# LoadBoard.net
KiCad netlist of a schematic drawn in EAGLE
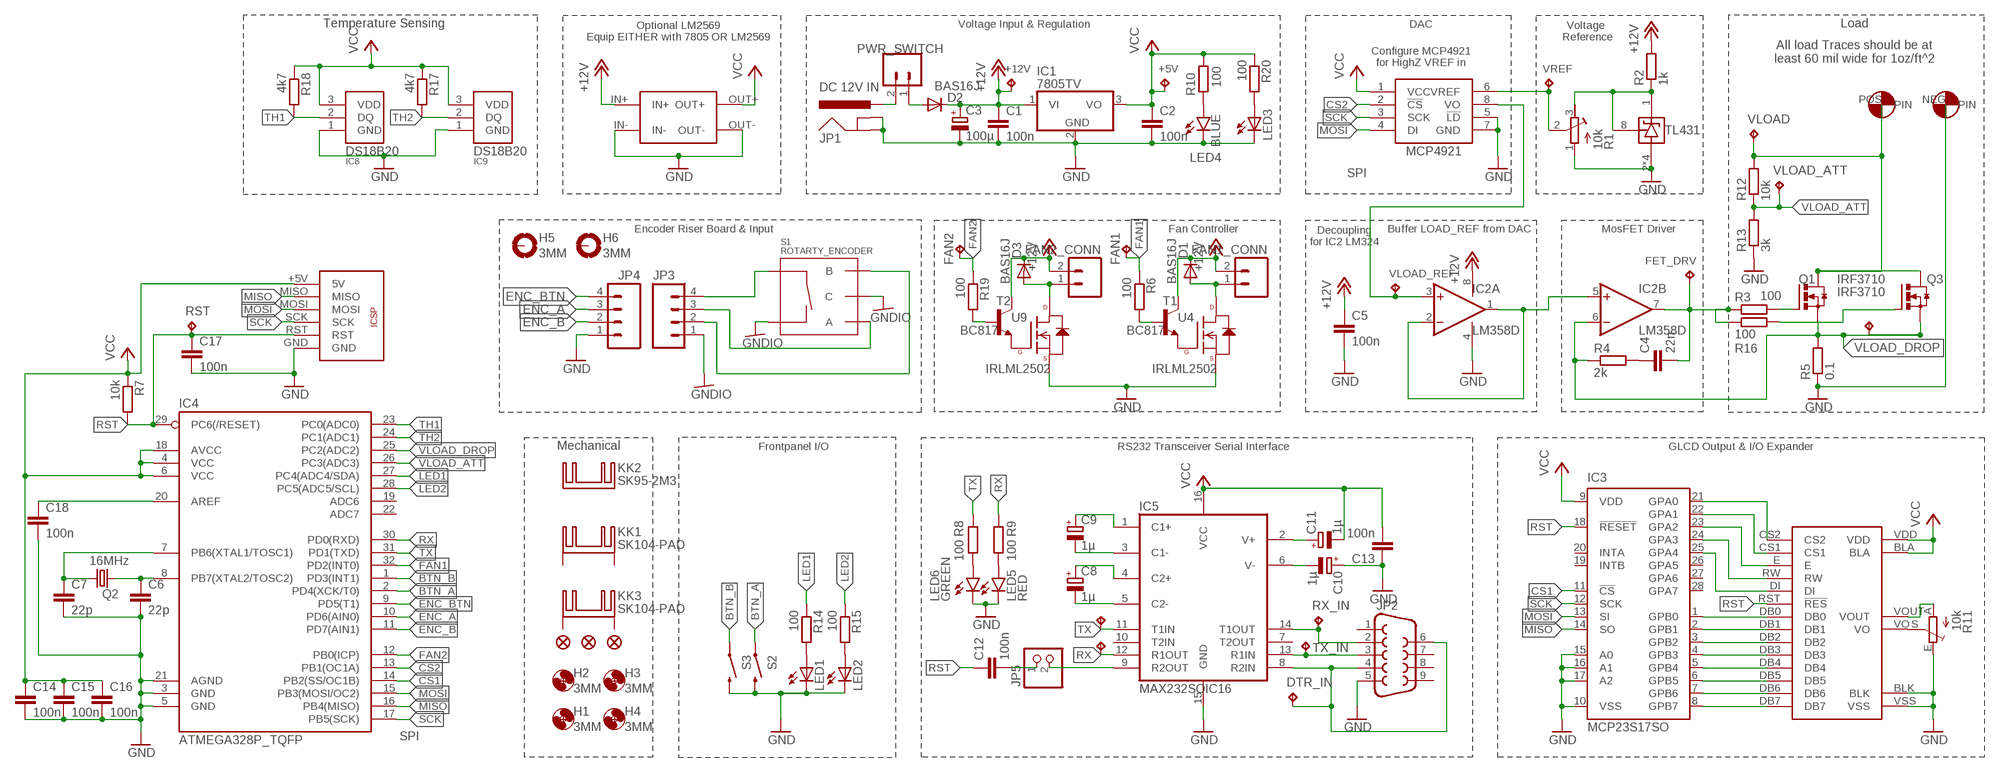
[diagram p0: schematic, sheet 1]

(export (version "E")
  (design (tool "Eeschema 10.0.6"))
  (components
    (comp (ref "+5V")
      (value "TPB1,27")
      (footprint "eagle-import:B1,27")
      (libsource (lib "eagle-import") (part "TPB1,27"))
    )
    (comp (ref "+12V")
      (value "TPB1,27")
      (footprint "eagle-import:B1,27")
      (libsource (lib "eagle-import") (part "TPB1,27"))
    )
    (comp (ref "C1")
      (value "100n")
      (footprint "eagle-import:C1206K")
      (libsource (lib "eagle-import") (part "C-EUC1206K"))
    )
    (comp (ref "C2")
      (value "100n")
      (footprint "eagle-import:C1206K")
      (libsource (lib "eagle-import") (part "C-EUC1206K"))
    )
    (comp (ref "C3")
      (value "100µ")
      (footprint "eagle-import:175TMP-0808")
      (libsource (lib "eagle-import") (part "CPOL-EU175TMP-0808"))
    )
    (comp (ref "C4")
      (value "22n")
      (footprint "eagle-import:C1206")
      (libsource (lib "eagle-import") (part "C-EUC1206"))
    )
    (comp (ref "C5")
      (value "100n")
      (footprint "eagle-import:C1206K")
      (libsource (lib "eagle-import") (part "C-EUC1206K"))
    )
    (comp (ref "C6")
      (value "22p")
      (footprint "eagle-import:C1206K")
      (libsource (lib "eagle-import") (part "C-EUC1206K"))
    )
    (comp (ref "C7")
      (value "22p")
      (footprint "eagle-import:C1206K")
      (libsource (lib "eagle-import") (part "C-EUC1206K"))
    )
    (comp (ref "C8")
      (value "1µ")
      (footprint "eagle-import:153CLV-0405")
      (libsource (lib "eagle-import") (part "CPOL-EU153CLV-0405"))
    )
    (comp (ref "C9")
      (value "1µ")
      (footprint "eagle-import:153CLV-0405")
      (libsource (lib "eagle-import") (part "CPOL-EU153CLV-0405"))
    )
    (comp (ref "C10")
      (value "1µ")
      (footprint "eagle-import:153CLV-0405")
      (libsource (lib "eagle-import") (part "CPOL-EU153CLV-0405"))
    )
    (comp (ref "C11")
      (value "1µ")
      (footprint "eagle-import:153CLV-0405")
      (libsource (lib "eagle-import") (part "CPOL-EU153CLV-0405"))
    )
    (comp (ref "C12")
      (value "100n")
      (footprint "eagle-import:C1206K")
      (libsource (lib "eagle-import") (part "C-EUC1206K"))
    )
    (comp (ref "C13")
      (value "100n")
      (footprint "eagle-import:C1206K")
      (libsource (lib "eagle-import") (part "C-EUC1206K"))
    )
    (comp (ref "C14")
      (value "100n")
      (footprint "eagle-import:C1206K")
      (libsource (lib "eagle-import") (part "C-EUC1206K"))
    )
    (comp (ref "C15")
      (value "100n")
      (footprint "eagle-import:C1206K")
      (libsource (lib "eagle-import") (part "C-EUC1206K"))
    )
    (comp (ref "C16")
      (value "100n")
      (footprint "eagle-import:C1206K")
      (libsource (lib "eagle-import") (part "C-EUC1206K"))
    )
    (comp (ref "C17")
      (value "100n")
      (footprint "eagle-import:C1206K")
      (libsource (lib "eagle-import") (part "C-EUC1206K"))
    )
    (comp (ref "C18")
      (value "100n")
      (footprint "eagle-import:C1206K")
      (libsource (lib "eagle-import") (part "C-EUC1206K"))
    )
    (comp (ref "D1")
      (value "BAS16J")
      (footprint "eagle-import:SOD323-W")
      (libsource (lib "eagle-import") (part "DIODE-SOD323-W"))
    )
    (comp (ref "D2")
      (value "BAS16J")
      (footprint "eagle-import:SOD323-W")
      (libsource (lib "eagle-import") (part "DIODE-SOD323-W"))
    )
    (comp (ref "D3")
      (value "BAS16J")
      (footprint "eagle-import:SOD323-W")
      (libsource (lib "eagle-import") (part "DIODE-SOD323-W"))
    )
    (comp (ref "DTR_IN")
      (value "TPB1,27")
      (footprint "eagle-import:B1,27")
      (libsource (lib "eagle-import") (part "TPB1,27"))
    )
    (comp (ref "FAN1")
      (value "TPB1,27")
      (footprint "eagle-import:B1,27")
      (libsource (lib "eagle-import") (part "TPB1,27"))
    )
    (comp (ref "FAN1_CONN")
      (value "M02POLAR")
      (footprint "eagle-import:MOLEX-1X2")
      (libsource (lib "eagle-import") (part "M02POLAR"))
    )
    (comp (ref "FAN2")
      (value "TPB1,27")
      (footprint "eagle-import:B1,27")
      (libsource (lib "eagle-import") (part "TPB1,27"))
    )
    (comp (ref "FAN2_CONN")
      (value "M02POLAR")
      (footprint "eagle-import:MOLEX-1X2")
      (libsource (lib "eagle-import") (part "M02POLAR"))
    )
    (comp (ref "FET_DRV")
      (value "TPB1,27")
      (footprint "eagle-import:B1,27")
      (libsource (lib "eagle-import") (part "TPB1,27"))
    )
    (comp (ref "FID1")
      (value "FIDUCIAL1X2")
      (footprint "eagle-import:FIDUCIAL-1X2")
      (libsource (lib "eagle-import") (part "FIDUCIAL1X2"))
    )
    (comp (ref "FID2")
      (value "FIDUCIAL1X2")
      (footprint "eagle-import:FIDUCIAL-1X2")
      (libsource (lib "eagle-import") (part "FIDUCIAL1X2"))
    )
    (comp (ref "FID3")
      (value "FIDUCIAL1X2")
      (footprint "eagle-import:FIDUCIAL-1X2")
      (libsource (lib "eagle-import") (part "FIDUCIAL1X2"))
    )
    (comp (ref "H1")
      (value "3MM")
      (footprint "eagle-import:3,0")
      (libsource (lib "eagle-import") (part "MOUNT-HOLE3.0"))
    )
    (comp (ref "H2")
      (value "3MM")
      (footprint "eagle-import:3,0")
      (libsource (lib "eagle-import") (part "MOUNT-HOLE3.0"))
    )
    (comp (ref "H3")
      (value "3MM")
      (footprint "eagle-import:3,0")
      (libsource (lib "eagle-import") (part "MOUNT-HOLE3.0"))
    )
    (comp (ref "H4")
      (value "3MM")
      (footprint "eagle-import:3,0")
      (libsource (lib "eagle-import") (part "MOUNT-HOLE3.0"))
    )
    (comp (ref "H5")
      (value "3MM")
      (footprint "eagle-import:3,0-PAD")
      (libsource (lib "eagle-import") (part "MOUNT-PAD-ROUND3.0"))
    )
    (comp (ref "H6")
      (value "3MM")
      (footprint "eagle-import:3,0-PAD")
      (libsource (lib "eagle-import") (part "MOUNT-PAD-ROUND3.0"))
    )
    (comp (ref "IC1")
      (value "7805TV")
      (footprint "eagle-import:TO220V")
      (libsource (lib "eagle-import") (part "78TV05"))
    )
    (comp (ref "IC2")
      (value "LM358D")
      (footprint "eagle-import:SO08")
      (libsource (lib "eagle-import") (part "LM358D"))
    )
    (comp (ref "IC3")
      (value "MCP23S17SO")
      (footprint "eagle-import:SO28W")
      (fields (field (name "MF") "MICROCHIP") (field (name "MPN") "MCP23S17-E/SO"))
      (libsource (lib "eagle-import") (part "MCP23S17SO"))
    )
    (comp (ref "IC4")
      (value "ATMEGA328P_TQFP")
      (footprint "eagle-import:TQFP32-08")
      (libsource (lib "eagle-import") (part "ATMEGA328P_TQFP"))
    )
    (comp (ref "IC5")
      (value "MAX232SOIC16")
      (footprint "eagle-import:SO016")
      (libsource (lib "eagle-import") (part "MAX232SOIC16"))
    )
    (comp (ref "IC6")
      (value "MCP4921")
      (footprint "eagle-import:SO-8")
      (libsource (lib "eagle-import") (part "MCP4921"))
    )
    (comp (ref "IC7")
      (value "TL431CD")
      (footprint "eagle-import:SO-8")
      (libsource (lib "eagle-import") (part "TL431CD"))
    )
    (comp (ref "IC8")
      (value "DS18B20")
      (footprint "eagle-import:TO-92")
      (libsource (lib "eagle-import") (part "DS18B20"))
    )
    (comp (ref "IC9")
      (value "DS18B20")
      (footprint "eagle-import:TO-92")
      (libsource (lib "eagle-import") (part "DS18B20"))
    )
    (comp (ref "JP1")
      (value "DC 12V IN")
      (footprint "eagle-import:POWER_JACK_PTH")
      (libsource (lib "eagle-import") (part "POWER_JACKPTH"))
    )
    (comp (ref "JP2")
      (value "DB9FEMALE")
      (footprint "eagle-import:DB9")
      (libsource (lib "eagle-import") (part "DB9FEMALE"))
    )
    (comp (ref "JP3")
      (value "M04POLAR")
      (footprint "eagle-import:MOLEX-1X4")
      (libsource (lib "eagle-import") (part "M04POLAR"))
    )
    (comp (ref "JP4")
      (value "M04POLAR")
      (footprint "eagle-import:MOLEX-1X4")
      (libsource (lib "eagle-import") (part "M04POLAR"))
    )
    (comp (ref "JP5")
      (value "PINHD-1X2")
      (footprint "eagle-import:1X02")
      (libsource (lib "eagle-import") (part "PINHD-1X2"))
    )
    (comp (ref "KK1")
      (value "SK104-PAD")
      (footprint "eagle-import:SK104-PAD")
      (libsource (lib "eagle-import") (part "SK104-PAD"))
    )
    (comp (ref "KK2")
      (value "SK95-2M3")
      (footprint "eagle-import:SK95-2M3")
      (libsource (lib "eagle-import") (part "SK95-2M3"))
    )
    (comp (ref "KK3")
      (value "SK104-PAD")
      (footprint "eagle-import:SK104-PAD")
      (libsource (lib "eagle-import") (part "SK104-PAD"))
    )
    (comp (ref "LED1")
      (value "LEDB155")
      (footprint "eagle-import:Q62902-B155")
      (libsource (lib "eagle-import") (part "LEDB155"))
    )
    (comp (ref "LED2")
      (value "LEDB155")
      (footprint "eagle-import:Q62902-B155")
      (libsource (lib "eagle-import") (part "LEDB155"))
    )
    (comp (ref "LED3")
      (value "LEDB155")
      (footprint "eagle-import:Q62902-B155")
      (libsource (lib "eagle-import") (part "LEDB155"))
    )
    (comp (ref "LED4")
      (value "BLUE")
      (footprint "eagle-import:LED-0603")
      (libsource (lib "eagle-import") (part "LED0603"))
    )
    (comp (ref "LED5")
      (value "RED")
      (footprint "eagle-import:LED-0603")
      (libsource (lib "eagle-import") (part "LED0603"))
    )
    (comp (ref "LED6")
      (value "GREEN")
      (footprint "eagle-import:LED-0603")
      (libsource (lib "eagle-import") (part "LED0603"))
    )
    (comp (ref "PWR_SWITCH")
      (value "M02POLAR")
      (footprint "eagle-import:MOLEX-1X2")
      (libsource (lib "eagle-import") (part "M02POLAR"))
    )
    (comp (ref "Q1")
      (value "IRF3710")
      (footprint "eagle-import:TO-220-V")
      (libsource (lib "eagle-import") (part "IRFZ44N"))
    )
    (comp (ref "Q2")
      (value "16MHz")
      (footprint "eagle-import:HC49UP")
      (libsource (lib "eagle-import") (part "CRYSTALHC49UP"))
    )
    (comp (ref "Q3")
      (value "IRF3710")
      (footprint "eagle-import:TO-220-V")
      (libsource (lib "eagle-import") (part "IRFZ44N"))
    )
    (comp (ref "R1")
      (value "10k")
      (footprint "eagle-import:RTRIM3296Y")
      (libsource (lib "eagle-import") (part "R-TRIMM3296Y"))
    )
    (comp (ref "R2")
      (value "1k")
      (footprint "eagle-import:M1206")
      (libsource (lib "eagle-import") (part "R-EU_M1206"))
    )
    (comp (ref "R3")
      (value "100")
      (footprint "eagle-import:R1206")
      (libsource (lib "eagle-import") (part "R-EU_R1206"))
    )
    (comp (ref "R4")
      (value "2k")
      (footprint "eagle-import:R1206")
      (libsource (lib "eagle-import") (part "R-EU_R1206"))
    )
    (comp (ref "R5")
      (value "0.1")
      (footprint "eagle-import:VTA52")
      (libsource (lib "eagle-import") (part "R-EU_VTA52"))
    )
    (comp (ref "R6")
      (value "100")
      (footprint "eagle-import:R1206")
      (libsource (lib "eagle-import") (part "R-EU_R1206"))
    )
    (comp (ref "R7")
      (value "10k")
      (footprint "eagle-import:R1206")
      (libsource (lib "eagle-import") (part "R-EU_R1206"))
    )
    (comp (ref "R8")
      (value "100")
      (footprint "eagle-import:R1206")
      (libsource (lib "eagle-import") (part "R-EU_R1206"))
    )
    (comp (ref "R9")
      (value "100")
      (footprint "eagle-import:R1206")
      (libsource (lib "eagle-import") (part "R-EU_R1206"))
    )
    (comp (ref "R10")
      (value "100")
      (footprint "eagle-import:R1206")
      (libsource (lib "eagle-import") (part "R-EU_R1206"))
    )
    (comp (ref "R11")
      (value "10k")
      (footprint "eagle-import:RS3")
      (libsource (lib "eagle-import") (part "TRIM_EU-RS3"))
    )
    (comp (ref "R12")
      (value "10k")
      (footprint "eagle-import:R1206")
      (libsource (lib "eagle-import") (part "R-EU_R1206"))
    )
    (comp (ref "R13")
      (value "3k")
      (footprint "eagle-import:R1206")
      (libsource (lib "eagle-import") (part "R-EU_R1206"))
    )
    (comp (ref "R14")
      (value "100")
      (footprint "eagle-import:R1206")
      (libsource (lib "eagle-import") (part "R-EU_R1206"))
    )
    (comp (ref "R15")
      (value "100")
      (footprint "eagle-import:R1206")
      (libsource (lib "eagle-import") (part "R-EU_R1206"))
    )
    (comp (ref "R16")
      (value "100")
      (footprint "eagle-import:R1206")
      (libsource (lib "eagle-import") (part "R-EU_R1206"))
    )
    (comp (ref "R17")
      (value "4k7")
      (footprint "eagle-import:M1206")
      (libsource (lib "eagle-import") (part "R-EU_M1206"))
    )
    (comp (ref "R18")
      (value "4k7")
      (footprint "eagle-import:M1206")
      (libsource (lib "eagle-import") (part "R-EU_M1206"))
    )
    (comp (ref "R19")
      (value "100")
      (footprint "eagle-import:R1206")
      (libsource (lib "eagle-import") (part "R-EU_R1206"))
    )
    (comp (ref "R20")
      (value "100")
      (footprint "eagle-import:R1206")
      (libsource (lib "eagle-import") (part "R-EU_R1206"))
    )
    (comp (ref "RST")
      (value "TPB1,27")
      (footprint "eagle-import:B1,27")
      (libsource (lib "eagle-import") (part "TPB1,27"))
    )
    (comp (ref "RX")
      (value "TPB1,27")
      (footprint "eagle-import:B1,27")
      (libsource (lib "eagle-import") (part "TPB1,27"))
    )
    (comp (ref "RX_IN")
      (value "TPB1,27")
      (footprint "eagle-import:B1,27")
      (libsource (lib "eagle-import") (part "TPB1,27"))
    )
    (comp (ref "S1")
      (value "ROTARTY_ENCODER")
      (footprint "eagle-import:ROTARY_ENC_PLAIN")
      (libsource (lib "eagle-import") (part "ROTARTY_ENCODER"))
    )
    (comp (ref "S2")
      (value "SWITCH-MOMENTARY-2SIDE_EZ")
      (footprint "eagle-import:TACTILE-PTH-SIDEEZ")
      (libsource (lib "eagle-import") (part "SWITCH-MOMENTARY-2SIDE_EZ"))
    )
    (comp (ref "S3")
      (value "SWITCH-MOMENTARY-2SIDE_EZ")
      (footprint "eagle-import:TACTILE-PTH-SIDEEZ")
      (libsource (lib "eagle-import") (part "SWITCH-MOMENTARY-2SIDE_EZ"))
    )
    (comp (ref "T1")
      (value "BC817")
      (footprint "eagle-import:SOT23-BEC")
      (libsource (lib "eagle-import") (part "-NPN-SOT23-BECBC817"))
    )
    (comp (ref "T2")
      (value "BC817")
      (footprint "eagle-import:SOT23-BEC")
      (libsource (lib "eagle-import") (part "-NPN-SOT23-BECBC817"))
    )
    (comp (ref "TX")
      (value "TPB1,27")
      (footprint "eagle-import:B1,27")
      (libsource (lib "eagle-import") (part "TPB1,27"))
    )
    (comp (ref "TX_IN")
      (value "TPB1,27")
      (footprint "eagle-import:B1,27")
      (libsource (lib "eagle-import") (part "TPB1,27"))
    )
    (comp (ref "U$3")
      (value "CON-2-HIGAMP")
      (footprint "eagle-import:CON-HIGHAMP-0.3_")
      (libsource (lib "eagle-import") (part "CON-2-HIGAMP"))
    )
    (comp (ref "U$5")
      (value "ICSPTHROUGHHOLE")
      (footprint "eagle-import:ICSP-THROUGHHOLE")
      (libsource (lib "eagle-import") (part "ICSPTHROUGHHOLE"))
    )
    (comp (ref "U$6")
      (value "KS0108-GLCDS6B0108")
      (footprint "eagle-import:KS0108-S6B0108-GLCD")
      (libsource (lib "eagle-import") (part "KS0108-GLCDS6B0108"))
    )
    (comp (ref "U$10")
      (value "LM2569NO_OUTLINE")
      (footprint "eagle-import:LM2596_NO_OUTLINE")
      (libsource (lib "eagle-import") (part "LM2569NO_OUTLINE"))
    )
    (comp (ref "U4")
      (value "IRLML2502")
      (footprint "eagle-import:SOT23-3")
      (libsource (lib "eagle-import") (part "N-CHANNEL-MOSFET-BSS138"))
    )
    (comp (ref "U9")
      (value "IRLML2502")
      (footprint "eagle-import:SOT23-3")
      (libsource (lib "eagle-import") (part "N-CHANNEL-MOSFET-BSS138"))
    )
    (comp (ref "VLOAD")
      (value "TPB1,27")
      (footprint "eagle-import:B1,27")
      (libsource (lib "eagle-import") (part "TPB1,27"))
    )
    (comp (ref "VLOAD_ATT")
      (value "TPB1,27")
      (footprint "eagle-import:B1,27")
      (libsource (lib "eagle-import") (part "TPB1,27"))
    )
    (comp (ref "VLOAD_DROP")
      (value "TPB1,27")
      (footprint "eagle-import:B1,27")
      (libsource (lib "eagle-import") (part "TPB1,27"))
    )
    (comp (ref "VLOAD_REF")
      (value "TPB1,27")
      (footprint "eagle-import:B1,27")
      (libsource (lib "eagle-import") (part "TPB1,27"))
    )
    (comp (ref "VREF")
      (value "TPB1,27")
      (footprint "eagle-import:B1,27")
      (libsource (lib "eagle-import") (part "TPB1,27"))
    )
  )
  (nets
    (net (code "1") (name "+12V") (class "Default")
      (node (ref "+12V") (pin "TP") (pinfunction "TP_TP") (pintype "input"))
      (node (ref "C1") (pin "1") (pinfunction "1_1") (pintype "passive"))
      (node (ref "C3") (pin "+") (pinfunction "+_+") (pintype "passive"))
      (node (ref "C5") (pin "1") (pinfunction "1_1") (pintype "passive"))
      (node (ref "D1") (pin "C") (pinfunction "C_C") (pintype "passive"))
      (node (ref "D2") (pin "C") (pinfunction "C_C") (pintype "passive"))
      (node (ref "D3") (pin "C") (pinfunction "C_C") (pintype "passive"))
      (node (ref "FAN1_CONN") (pin "2") (pinfunction "2_2") (pintype "passive"))
      (node (ref "FAN2_CONN") (pin "2") (pinfunction "2_2") (pintype "passive"))
      (node (ref "IC1") (pin "1") (pinfunction "VI_1") (pintype "input"))
      (node (ref "IC2") (pin "8") (pinfunction "V+_8") (pintype "power_in"))
      (node (ref "R2") (pin "2") (pinfunction "2_2") (pintype "passive"))
      (node (ref "T1") (pin "C") (pinfunction "C_C") (pintype "passive"))
      (node (ref "T2") (pin "C") (pinfunction "C_C") (pintype "passive"))
      (node (ref "U$10") (pin "IN+") (pinfunction "IN+_IN+") (pintype "bidirectional"))
    )
    (net (code "2") (name "BTN_A") (class "Default")
      (node (ref "IC4") (pin "2") (pinfunction "PD4(XCK/T0)_2") (pintype "bidirectional"))
      (node (ref "S2") (pin "1") (pinfunction "1_1") (pintype "passive"))
    )
    (net (code "3") (name "BTN_B") (class "Default")
      (node (ref "IC4") (pin "1") (pinfunction "PD3(INT1)_1") (pintype "bidirectional"))
      (node (ref "S3") (pin "1") (pinfunction "1_1") (pintype "passive"))
    )
    (net (code "4") (name "CS1") (class "Default")
      (node (ref "IC3") (pin "11") (pinfunction "~{CS}_11") (pintype "input"))
      (node (ref "IC4") (pin "14") (pinfunction "PB2(SS/OC1B)_14") (pintype "bidirectional"))
    )
    (net (code "5") (name "CS2") (class "Default")
      (node (ref "IC4") (pin "13") (pinfunction "PB1(OC1A)_13") (pintype "bidirectional"))
      (node (ref "IC6") (pin "2") (pinfunction "~{CS}_2") (pintype "bidirectional"))
    )
    (net (code "6") (name "ENC_A") (class "Default")
      (node (ref "IC4") (pin "10") (pinfunction "PD6(AIN0)_10") (pintype "bidirectional"))
      (node (ref "JP4") (pin "3") (pinfunction "3_3") (pintype "passive"))
    )
    (net (code "7") (name "ENC_B") (class "Default")
      (node (ref "IC4") (pin "11") (pinfunction "PD7(AIN1)_11") (pintype "bidirectional"))
      (node (ref "JP4") (pin "2") (pinfunction "2_2") (pintype "passive"))
    )
    (net (code "8") (name "ENC_BTN") (class "Default")
      (node (ref "IC4") (pin "9") (pinfunction "PD5(T1)_9") (pintype "bidirectional"))
      (node (ref "JP4") (pin "4") (pinfunction "4_4") (pintype "passive"))
    )
    (net (code "9") (name "FAN1") (class "Default")
      (node (ref "FAN1") (pin "TP") (pinfunction "TP_TP") (pintype "input"))
      (node (ref "IC4") (pin "32") (pinfunction "PD2(INT0)_32") (pintype "bidirectional"))
      (node (ref "R6") (pin "1") (pinfunction "1_1") (pintype "passive"))
    )
    (net (code "10") (name "FAN2") (class "Default")
      (node (ref "FAN2") (pin "TP") (pinfunction "TP_TP") (pintype "input"))
      (node (ref "IC4") (pin "12") (pinfunction "PB0(ICP)_12") (pintype "bidirectional"))
      (node (ref "R19") (pin "1") (pinfunction "1_1") (pintype "passive"))
    )
    (net (code "11") (name "GND") (class "Default")
      (node (ref "C1") (pin "2") (pinfunction "2_2") (pintype "passive"))
      (node (ref "C10") (pin "+") (pinfunction "+_+") (pintype "passive"))
      (node (ref "C13") (pin "1") (pinfunction "1_1") (pintype "passive"))
      (node (ref "C14") (pin "2") (pinfunction "2_2") (pintype "passive"))
      (node (ref "C15") (pin "2") (pinfunction "2_2") (pintype "passive"))
      (node (ref "C16") (pin "2") (pinfunction "2_2") (pintype "passive"))
      (node (ref "C17") (pin "2") (pinfunction "2_2") (pintype "passive"))
      (node (ref "C18") (pin "2") (pinfunction "2_2") (pintype "passive"))
      (node (ref "C2") (pin "2") (pinfunction "2_2") (pintype "passive"))
      (node (ref "C3") (pin "-") (pinfunction "-_-") (pintype "passive"))
      (node (ref "C5") (pin "2") (pinfunction "2_2") (pintype "passive"))
      (node (ref "C6") (pin "2") (pinfunction "2_2") (pintype "passive"))
      (node (ref "C7") (pin "2") (pinfunction "2_2") (pintype "passive"))
      (node (ref "IC1") (pin "2") (pinfunction "GND_2") (pintype "passive"))
      (node (ref "IC2") (pin "4") (pinfunction "V-_4") (pintype "power_in"))
      (node (ref "IC3") (pin "10") (pinfunction "VSS_10") (pintype "power_in"))
      (node (ref "IC3") (pin "15") (pinfunction "A0_15") (pintype "input"))
      (node (ref "IC3") (pin "16") (pinfunction "A1_16") (pintype "input"))
      (node (ref "IC3") (pin "17") (pinfunction "A2_17") (pintype "input"))
      (node (ref "IC4") (pin "21") (pinfunction "AGND_21") (pintype "bidirectional"))
      (node (ref "IC4") (pin "3") (pinfunction "GND_3") (pintype "bidirectional"))
      (node (ref "IC4") (pin "5") (pinfunction "GND_5") (pintype "bidirectional"))
      (node (ref "IC5") (pin "15") (pinfunction "GND_15") (pintype "bidirectional"))
      (node (ref "IC6") (pin "5") (pinfunction "~{LD}_5") (pintype "input"))
      (node (ref "IC6") (pin "7") (pinfunction "GND_7") (pintype "power_in"))
      (node (ref "IC7") (pin "2") (pinfunction "ANODE_2") (pintype "passive"))
      (node (ref "IC7") (pin "3") (pinfunction "ANODE_3") (pintype "passive"))
      (node (ref "IC7") (pin "6") (pinfunction "ANODE_6") (pintype "passive"))
      (node (ref "IC7") (pin "7") (pinfunction "ANODE_7") (pintype "passive"))
      (node (ref "IC8") (pin "1") (pinfunction "GND_1") (pintype "power_in"))
      (node (ref "IC9") (pin "1") (pinfunction "GND_1") (pintype "power_in"))
      (node (ref "JP1") (pin "GND") (pinfunction "GND_GND") (pintype "bidirectional"))
      (node (ref "JP1") (pin "GNDBREAK") (pinfunction "GNDBREAK_GNDBREAK") (pintype "bidirectional"))
      (node (ref "JP2") (pin "5") (pinfunction "5_5") (pintype "passive"))
      (node (ref "JP4") (pin "1") (pinfunction "1_1") (pintype "passive"))
      (node (ref "LED1") (pin "K") (pinfunction "C_K") (pintype "passive"))
      (node (ref "LED2") (pin "K") (pinfunction "C_K") (pintype "passive"))
      (node (ref "LED3") (pin "K") (pinfunction "C_K") (pintype "passive"))
      (node (ref "LED4") (pin "C") (pinfunction "C_C") (pintype "passive"))
      (node (ref "LED5") (pin "C") (pinfunction "C_C") (pintype "passive"))
      (node (ref "LED6") (pin "C") (pinfunction "C_C") (pintype "passive"))
      (node (ref "R1") (pin "1") (pinfunction "A_1") (pintype "passive"))
      (node (ref "R11") (pin "E") (pinfunction "E_E") (pintype "passive"))
      (node (ref "R13") (pin "1") (pinfunction "1_1") (pintype "passive"))
      (node (ref "R5") (pin "1") (pinfunction "1_1") (pintype "passive"))
      (node (ref "S2") (pin "2") (pinfunction "2_2") (pintype "passive"))
      (node (ref "S3") (pin "2") (pinfunction "2_2") (pintype "passive"))
      (node (ref "U$10") (pin "IN-") (pinfunction "IN-_IN-") (pintype "bidirectional"))
      (node (ref "U$10") (pin "OUT-") (pinfunction "OUT-_OUT-") (pintype "bidirectional"))
      (node (ref "U$3") (pin "NEG") (pinfunction "PIN_NEG") (pintype "bidirectional"))
      (node (ref "U$5") (pin "GND") (pinfunction "GND_GND") (pintype "bidirectional"))
      (node (ref "U$6") (pin "BLK") (pinfunction "BLK_BLK") (pintype "bidirectional"))
      (node (ref "U$6") (pin "VSS") (pinfunction "VSS_VSS") (pintype "bidirectional"))
      (node (ref "U4") (pin "2") (pinfunction "S_2") (pintype "passive"))
      (node (ref "U9") (pin "2") (pinfunction "S_2") (pintype "passive"))
    )
    (net (code "12") (name "GNDIO") (class "Default")
      (node (ref "JP3") (pin "1") (pinfunction "1_1") (pintype "passive"))
      (node (ref "S1") (pin "C") (pinfunction "C_C") (pintype "bidirectional"))
      (node (ref "S1") (pin "SW-") (pinfunction "SW-_SW-") (pintype "bidirectional"))
    )
    (net (code "13") (name "LED1") (class "Default")
      (node (ref "IC4") (pin "27") (pinfunction "PC4(ADC4/SDA)_27") (pintype "bidirectional"))
      (node (ref "R14") (pin "1") (pinfunction "1_1") (pintype "passive"))
    )
    (net (code "14") (name "LED2") (class "Default")
      (node (ref "IC4") (pin "28") (pinfunction "PC5(ADC5/SCL)_28") (pintype "bidirectional"))
      (node (ref "R15") (pin "1") (pinfunction "1_1") (pintype "passive"))
    )
    (net (code "15") (name "MISO") (class "Default")
      (node (ref "IC3") (pin "14") (pinfunction "SO_14") (pintype "output"))
      (node (ref "IC4") (pin "16") (pinfunction "PB4(MISO)_16") (pintype "bidirectional"))
      (node (ref "U$5") (pin "MISO") (pinfunction "MISO_MISO") (pintype "bidirectional"))
    )
    (net (code "16") (name "MOSI") (class "Default")
      (node (ref "IC3") (pin "13") (pinfunction "SI_13") (pintype "input"))
      (node (ref "IC4") (pin "15") (pinfunction "PB3(MOSI/OC2)_15") (pintype "bidirectional"))
      (node (ref "IC6") (pin "4") (pinfunction "DI_4") (pintype "bidirectional"))
      (node (ref "U$5") (pin "MOSI") (pinfunction "MOSI_MOSI") (pintype "bidirectional"))
    )
    (net (code "17") (name "Net-(C4-Pad1)") (class "Default")
      (node (ref "C4") (pin "1") (pinfunction "1_1") (pintype "passive"))
      (node (ref "R4") (pin "2") (pinfunction "2_2") (pintype "passive"))
    )
    (net (code "18") (name "Net-(C12-Pad2)") (class "Default")
      (node (ref "C12") (pin "2") (pinfunction "2_2") (pintype "passive"))
      (node (ref "JP5") (pin "1") (pinfunction "1_1") (pintype "passive"))
    )
    (net (code "19") (name "Net-(D2-PadA)") (class "Default")
      (node (ref "D2") (pin "A") (pinfunction "A_A") (pintype "passive"))
      (node (ref "PWR_SWITCH") (pin "1") (pinfunction "1_1") (pintype "passive"))
    )
    (net (code "20") (name "Net-(IC2A-+IN)") (class "Default")
      (node (ref "IC2") (pin "3") (pinfunction "+IN_3") (pintype "input"))
      (node (ref "IC6") (pin "8") (pinfunction "VO_8") (pintype "output"))
      (node (ref "VLOAD_REF") (pin "TP") (pinfunction "TP_TP") (pintype "input"))
    )
    (net (code "21") (name "Net-(IC2A--IN)") (class "Default")
      (node (ref "IC2") (pin "1") (pinfunction "OUT_1") (pintype "output"))
      (node (ref "IC2") (pin "2") (pinfunction "-IN_2") (pintype "input"))
      (node (ref "IC2") (pin "5") (pinfunction "+IN_5") (pintype "input"))
    )
    (net (code "22") (name "Net-(IC2B-OUT)") (class "Default")
      (node (ref "C4") (pin "2") (pinfunction "2_2") (pintype "passive"))
      (node (ref "FET_DRV") (pin "TP") (pinfunction "TP_TP") (pintype "input"))
      (node (ref "IC2") (pin "7") (pinfunction "OUT_7") (pintype "output"))
      (node (ref "R16") (pin "1") (pinfunction "1_1") (pintype "passive"))
      (node (ref "R3") (pin "1") (pinfunction "1_1") (pintype "passive"))
    )
    (net (code "23") (name "Net-(IC3-GPA0)") (class "Default")
      (node (ref "IC3") (pin "21") (pinfunction "GPA0_21") (pintype "bidirectional"))
      (node (ref "U$6") (pin "CS2") (pinfunction "CS2_CS2") (pintype "bidirectional"))
    )
    (net (code "24") (name "Net-(IC3-GPA1)") (class "Default")
      (node (ref "IC3") (pin "22") (pinfunction "GPA1_22") (pintype "bidirectional"))
      (node (ref "U$6") (pin "CS1") (pinfunction "CS1_CS1") (pintype "bidirectional"))
    )
    (net (code "25") (name "Net-(IC3-GPA2)") (class "Default")
      (node (ref "IC3") (pin "23") (pinfunction "GPA2_23") (pintype "bidirectional"))
      (node (ref "U$6") (pin "E") (pinfunction "E_E") (pintype "bidirectional"))
    )
    (net (code "26") (name "Net-(IC3-GPA3)") (class "Default")
      (node (ref "IC3") (pin "24") (pinfunction "GPA3_24") (pintype "bidirectional"))
      (node (ref "U$6") (pin "RW") (pinfunction "RW_RW") (pintype "bidirectional"))
    )
    (net (code "27") (name "Net-(IC3-GPA4)") (class "Default")
      (node (ref "IC3") (pin "25") (pinfunction "GPA4_25") (pintype "bidirectional"))
      (node (ref "U$6") (pin "DI") (pinfunction "DI_DI") (pintype "bidirectional"))
    )
    (net (code "28") (name "Net-(IC3-GPB0)") (class "Default")
      (node (ref "IC3") (pin "1") (pinfunction "GPB0_1") (pintype "bidirectional"))
      (node (ref "U$6") (pin "DB0") (pinfunction "DB0_DB0") (pintype "bidirectional"))
    )
    (net (code "29") (name "Net-(IC3-GPB1)") (class "Default")
      (node (ref "IC3") (pin "2") (pinfunction "GPB1_2") (pintype "bidirectional"))
      (node (ref "U$6") (pin "DB1") (pinfunction "DB1_DB1") (pintype "bidirectional"))
    )
    (net (code "30") (name "Net-(IC3-GPB2)") (class "Default")
      (node (ref "IC3") (pin "3") (pinfunction "GPB2_3") (pintype "bidirectional"))
      (node (ref "U$6") (pin "DB2") (pinfunction "DB2_DB2") (pintype "bidirectional"))
    )
    (net (code "31") (name "Net-(IC3-GPB3)") (class "Default")
      (node (ref "IC3") (pin "4") (pinfunction "GPB3_4") (pintype "bidirectional"))
      (node (ref "U$6") (pin "DB3") (pinfunction "DB3_DB3") (pintype "bidirectional"))
    )
    (net (code "32") (name "Net-(IC3-GPB4)") (class "Default")
      (node (ref "IC3") (pin "5") (pinfunction "GPB4_5") (pintype "bidirectional"))
      (node (ref "U$6") (pin "DB4") (pinfunction "DB4_DB4") (pintype "bidirectional"))
    )
    (net (code "33") (name "Net-(IC3-GPB5)") (class "Default")
      (node (ref "IC3") (pin "6") (pinfunction "GPB5_6") (pintype "bidirectional"))
      (node (ref "U$6") (pin "DB5") (pinfunction "DB5_DB5") (pintype "bidirectional"))
    )
    (net (code "34") (name "Net-(IC3-GPB6)") (class "Default")
      (node (ref "IC3") (pin "7") (pinfunction "GPB6_7") (pintype "bidirectional"))
      (node (ref "U$6") (pin "DB6") (pinfunction "DB6_DB6") (pintype "bidirectional"))
    )
    (net (code "35") (name "Net-(IC3-GPB7)") (class "Default")
      (node (ref "IC3") (pin "8") (pinfunction "GPB7_8") (pintype "bidirectional"))
      (node (ref "U$6") (pin "DB7") (pinfunction "DB7_DB7") (pintype "bidirectional"))
    )
    (net (code "36") (name "Net-(IC4-AREF)") (class "Default")
      (node (ref "C18") (pin "1") (pinfunction "1_1") (pintype "passive"))
      (node (ref "IC4") (pin "20") (pinfunction "AREF_20") (pintype "bidirectional"))
    )
    (net (code "37") (name "Net-(IC4-PB6(XTAL1{slash}TOSC1))") (class "Default")
      (node (ref "C7") (pin "1") (pinfunction "1_1") (pintype "passive"))
      (node (ref "IC4") (pin "7") (pinfunction "PB6(XTAL1/TOSC1)_7") (pintype "bidirectional"))
      (node (ref "Q2") (pin "1") (pinfunction "1_1") (pintype "passive"))
    )
    (net (code "38") (name "Net-(IC4-PB7(XTAL2{slash}TOSC2))") (class "Default")
      (node (ref "C6") (pin "1") (pinfunction "1_1") (pintype "passive"))
      (node (ref "IC4") (pin "8") (pinfunction "PB7(XTAL2/TOSC2)_8") (pintype "bidirectional"))
      (node (ref "Q2") (pin "2") (pinfunction "2_2") (pintype "passive"))
    )
    (net (code "39") (name "Net-(IC5-C1+)") (class "Default")
      (node (ref "C9") (pin "+") (pinfunction "+_+") (pintype "passive"))
      (node (ref "IC5") (pin "1") (pinfunction "C1+_1") (pintype "bidirectional"))
    )
    (net (code "40") (name "Net-(IC5-C1-)") (class "Default")
      (node (ref "C9") (pin "-") (pinfunction "-_-") (pintype "passive"))
      (node (ref "IC5") (pin "3") (pinfunction "C1-_3") (pintype "bidirectional"))
    )
    (net (code "41") (name "Net-(IC5-C2+)") (class "Default")
      (node (ref "C8") (pin "+") (pinfunction "+_+") (pintype "passive"))
      (node (ref "IC5") (pin "4") (pinfunction "C2+_4") (pintype "bidirectional"))
    )
    (net (code "42") (name "Net-(IC5-C2-)") (class "Default")
      (node (ref "C8") (pin "-") (pinfunction "-_-") (pintype "passive"))
      (node (ref "IC5") (pin "5") (pinfunction "C2-_5") (pintype "bidirectional"))
    )
    (net (code "43") (name "Net-(IC5-R1IN)") (class "Default")
      (node (ref "IC5") (pin "13") (pinfunction "R1IN_13") (pintype "input"))
      (node (ref "JP2") (pin "3") (pinfunction "3_3") (pintype "passive"))
      (node (ref "TX_IN") (pin "TP") (pinfunction "TP_TP") (pintype "input"))
    )
    (net (code "44") (name "Net-(IC5-R2IN)") (class "Default")
      (node (ref "DTR_IN") (pin "TP") (pinfunction "TP_TP") (pintype "input"))
      (node (ref "IC5") (pin "8") (pinfunction "R2IN_8") (pintype "input"))
      (node (ref "JP2") (pin "4") (pinfunction "4_4") (pintype "passive"))
      (node (ref "JP2") (pin "6") (pinfunction "6_6") (pintype "passive"))
    )
    (net (code "45") (name "Net-(IC5-R2OUT)") (class "Default")
      (node (ref "IC5") (pin "9") (pinfunction "R2OUT_9") (pintype "output"))
      (node (ref "JP5") (pin "2") (pinfunction "2_2") (pintype "passive"))
    )
    (net (code "46") (name "Net-(IC5-T1OUT)") (class "Default")
      (node (ref "IC5") (pin "14") (pinfunction "T1OUT_14") (pintype "output"))
      (node (ref "JP2") (pin "2") (pinfunction "2_2") (pintype "passive"))
      (node (ref "RX_IN") (pin "TP") (pinfunction "TP_TP") (pintype "input"))
    )
    (net (code "47") (name "Net-(IC5-V+)") (class "Default")
      (node (ref "C11") (pin "+") (pinfunction "+_+") (pintype "passive"))
      (node (ref "IC5") (pin "2") (pinfunction "V+_2") (pintype "bidirectional"))
    )
    (net (code "48") (name "Net-(IC5-V-)") (class "Default")
      (node (ref "C10") (pin "-") (pinfunction "-_-") (pintype "passive"))
      (node (ref "IC5") (pin "6") (pinfunction "V-_6") (pintype "bidirectional"))
    )
    (net (code "49") (name "Net-(IC6-VREF)") (class "Default")
      (node (ref "IC6") (pin "6") (pinfunction "VREF_6") (pintype "input"))
      (node (ref "R1") (pin "2") (pinfunction "S_2") (pintype "passive"))
      (node (ref "VREF") (pin "TP") (pinfunction "TP_TP") (pintype "input"))
    )
    (net (code "50") (name "Net-(IC7-CATHODE)") (class "Default")
      (node (ref "IC7") (pin "1") (pinfunction "CATHODE_1") (pintype "passive"))
      (node (ref "IC7") (pin "8") (pinfunction "REF_8") (pintype "passive"))
      (node (ref "R1") (pin "3") (pinfunction "E_3") (pintype "passive"))
      (node (ref "R2") (pin "1") (pinfunction "1_1") (pintype "passive"))
    )
    (net (code "51") (name "Net-(JP1-PadPWR)") (class "Default")
      (node (ref "JP1") (pin "PWR") (pinfunction "PWR_PWR") (pintype "bidirectional"))
      (node (ref "PWR_SWITCH") (pin "2") (pinfunction "2_2") (pintype "passive"))
    )
    (net (code "52") (name "Net-(JP3-Pad2)") (class "Default")
      (node (ref "JP3") (pin "2") (pinfunction "2_2") (pintype "passive"))
      (node (ref "S1") (pin "B") (pinfunction "B_B") (pintype "bidirectional"))
    )
    (net (code "53") (name "Net-(JP3-Pad3)") (class "Default")
      (node (ref "JP3") (pin "3") (pinfunction "3_3") (pintype "passive"))
      (node (ref "S1") (pin "A") (pinfunction "A_A") (pintype "bidirectional"))
    )
    (net (code "54") (name "Net-(JP3-Pad4)") (class "Default")
      (node (ref "JP3") (pin "4") (pinfunction "4_4") (pintype "passive"))
      (node (ref "S1") (pin "SW+") (pinfunction "SW+_SW+") (pintype "bidirectional"))
    )
    (net (code "55") (name "Net-(LED1-PadA)") (class "Default")
      (node (ref "LED1") (pin "A") (pinfunction "A_A") (pintype "passive"))
      (node (ref "R14") (pin "2") (pinfunction "2_2") (pintype "passive"))
    )
    (net (code "56") (name "Net-(LED2-PadA)") (class "Default")
      (node (ref "LED2") (pin "A") (pinfunction "A_A") (pintype "passive"))
      (node (ref "R15") (pin "2") (pinfunction "2_2") (pintype "passive"))
    )
    (net (code "57") (name "Net-(LED3-PadA)") (class "Default")
      (node (ref "LED3") (pin "A") (pinfunction "A_A") (pintype "passive"))
      (node (ref "R20") (pin "2") (pinfunction "2_2") (pintype "passive"))
    )
    (net (code "58") (name "Net-(LED4-PadA)") (class "Default")
      (node (ref "LED4") (pin "A") (pinfunction "A_A") (pintype "passive"))
      (node (ref "R10") (pin "2") (pinfunction "2_2") (pintype "passive"))
    )
    (net (code "59") (name "Net-(LED5-PadA)") (class "Default")
      (node (ref "LED5") (pin "A") (pinfunction "A_A") (pintype "passive"))
      (node (ref "R9") (pin "2") (pinfunction "2_2") (pintype "passive"))
    )
    (net (code "60") (name "Net-(LED6-PadA)") (class "Default")
      (node (ref "LED6") (pin "A") (pinfunction "A_A") (pintype "passive"))
      (node (ref "R8") (pin "2") (pinfunction "2_2") (pintype "passive"))
    )
    (net (code "61") (name "Net-(Q1-D)") (class "Default")
      (node (ref "Q1") (pin "2") (pinfunction "D_2") (pintype "passive"))
      (node (ref "Q3") (pin "2") (pinfunction "D_2") (pintype "passive"))
      (node (ref "R12") (pin "2") (pinfunction "2_2") (pintype "passive"))
      (node (ref "U$3") (pin "POS") (pinfunction "PIN_POS") (pintype "bidirectional"))
      (node (ref "VLOAD") (pin "TP") (pinfunction "TP_TP") (pintype "input"))
    )
    (net (code "62") (name "Net-(Q1-G)") (class "Default")
      (node (ref "Q1") (pin "1") (pinfunction "G_1") (pintype "passive"))
      (node (ref "R3") (pin "2") (pinfunction "2_2") (pintype "passive"))
    )
    (net (code "63") (name "Net-(Q3-G)") (class "Default")
      (node (ref "Q3") (pin "1") (pinfunction "G_1") (pintype "passive"))
      (node (ref "R16") (pin "2") (pinfunction "2_2") (pintype "passive"))
    )
    (net (code "64") (name "Net-(R6-Pad2)") (class "Default")
      (node (ref "R6") (pin "2") (pinfunction "2_2") (pintype "passive"))
      (node (ref "T1") (pin "B") (pinfunction "B_B") (pintype "passive"))
    )
    (net (code "65") (name "Net-(R11-PadA)") (class "Default")
      (node (ref "R11") (pin "A") (pinfunction "A_A") (pintype "passive"))
      (node (ref "U$6") (pin "VOUT") (pinfunction "VOUT_VOUT") (pintype "bidirectional"))
    )
    (net (code "66") (name "Net-(R11-PadS)") (class "Default")
      (node (ref "R11") (pin "S") (pinfunction "S_S") (pintype "passive"))
      (node (ref "U$6") (pin "VO") (pinfunction "VO_VO") (pintype "bidirectional"))
    )
    (net (code "67") (name "Net-(R19-Pad2)") (class "Default")
      (node (ref "R19") (pin "2") (pinfunction "2_2") (pintype "passive"))
      (node (ref "T2") (pin "B") (pinfunction "B_B") (pintype "passive"))
    )
    (net (code "68") (name "Net-(U4-D)") (class "Default")
      (node (ref "D1") (pin "A") (pinfunction "A_A") (pintype "passive"))
      (node (ref "FAN1_CONN") (pin "1") (pinfunction "1_1") (pintype "passive"))
      (node (ref "U4") (pin "3") (pinfunction "D_3") (pintype "passive"))
    )
    (net (code "69") (name "Net-(U4-G)") (class "Default")
      (node (ref "T1") (pin "E") (pinfunction "E_E") (pintype "passive"))
      (node (ref "U4") (pin "1") (pinfunction "G_1") (pintype "passive"))
    )
    (net (code "70") (name "Net-(U9-D)") (class "Default")
      (node (ref "D3") (pin "A") (pinfunction "A_A") (pintype "passive"))
      (node (ref "FAN2_CONN") (pin "1") (pinfunction "1_1") (pintype "passive"))
      (node (ref "U9") (pin "3") (pinfunction "D_3") (pintype "passive"))
    )
    (net (code "71") (name "Net-(U9-G)") (class "Default")
      (node (ref "T2") (pin "E") (pinfunction "E_E") (pintype "passive"))
      (node (ref "U9") (pin "1") (pinfunction "G_1") (pintype "passive"))
    )
    (net (code "72") (name "RST") (class "Default")
      (node (ref "C12") (pin "1") (pinfunction "1_1") (pintype "passive"))
      (node (ref "C17") (pin "1") (pinfunction "1_1") (pintype "passive"))
      (node (ref "IC3") (pin "18") (pinfunction "~{RESET}_18") (pintype "input"))
      (node (ref "IC4") (pin "29") (pinfunction "PC6(/RESET)_29") (pintype "bidirectional"))
      (node (ref "R7") (pin "2") (pinfunction "2_2") (pintype "passive"))
      (node (ref "RST") (pin "TP") (pinfunction "TP_TP") (pintype "input"))
      (node (ref "U$5") (pin "RST") (pinfunction "RST_RST") (pintype "bidirectional"))
      (node (ref "U$6") (pin "RST") (pinfunction "~{RES}_RST") (pintype "bidirectional"))
    )
    (net (code "73") (name "RX") (class "Default")
      (node (ref "IC4") (pin "30") (pinfunction "PD0(RXD)_30") (pintype "bidirectional"))
      (node (ref "IC5") (pin "12") (pinfunction "R1OUT_12") (pintype "output"))
      (node (ref "R9") (pin "1") (pinfunction "1_1") (pintype "passive"))
      (node (ref "RX") (pin "TP") (pinfunction "TP_TP") (pintype "input"))
    )
    (net (code "74") (name "SCK") (class "Default")
      (node (ref "IC3") (pin "12") (pinfunction "SCK_12") (pintype "input"))
      (node (ref "IC4") (pin "17") (pinfunction "PB5(SCK)_17") (pintype "bidirectional"))
      (node (ref "IC6") (pin "3") (pinfunction "SCK_3") (pintype "bidirectional"))
      (node (ref "U$5") (pin "SCK") (pinfunction "SCK_SCK") (pintype "bidirectional"))
    )
    (net (code "75") (name "TH1") (class "Default")
      (node (ref "IC4") (pin "23") (pinfunction "PC0(ADC0)_23") (pintype "bidirectional"))
      (node (ref "IC8") (pin "2") (pinfunction "DQ_2") (pintype "bidirectional"))
      (node (ref "R18") (pin "2") (pinfunction "2_2") (pintype "passive"))
    )
    (net (code "76") (name "TH2") (class "Default")
      (node (ref "IC4") (pin "24") (pinfunction "PC1(ADC1)_24") (pintype "bidirectional"))
      (node (ref "IC9") (pin "2") (pinfunction "DQ_2") (pintype "bidirectional"))
      (node (ref "R17") (pin "2") (pinfunction "2_2") (pintype "passive"))
    )
    (net (code "77") (name "TX") (class "Default")
      (node (ref "IC4") (pin "31") (pinfunction "PD1(TXD)_31") (pintype "bidirectional"))
      (node (ref "IC5") (pin "11") (pinfunction "T1IN_11") (pintype "input"))
      (node (ref "R8") (pin "1") (pinfunction "1_1") (pintype "passive"))
      (node (ref "TX") (pin "TP") (pinfunction "TP_TP") (pintype "input"))
    )
    (net (code "78") (name "VCC") (class "Default")
      (node (ref "+5V") (pin "TP") (pinfunction "TP_TP") (pintype "input"))
      (node (ref "C11") (pin "-") (pinfunction "-_-") (pintype "passive"))
      (node (ref "C13") (pin "2") (pinfunction "2_2") (pintype "passive"))
      (node (ref "C14") (pin "1") (pinfunction "1_1") (pintype "passive"))
      (node (ref "C15") (pin "1") (pinfunction "1_1") (pintype "passive"))
      (node (ref "C16") (pin "1") (pinfunction "1_1") (pintype "passive"))
      (node (ref "C2") (pin "1") (pinfunction "1_1") (pintype "passive"))
      (node (ref "IC1") (pin "3") (pinfunction "VO_3") (pintype "passive"))
      (node (ref "IC3") (pin "9") (pinfunction "VDD_9") (pintype "power_in"))
      (node (ref "IC4") (pin "18") (pinfunction "AVCC_18") (pintype "bidirectional"))
      (node (ref "IC4") (pin "4") (pinfunction "VCC_4") (pintype "bidirectional"))
      (node (ref "IC4") (pin "6") (pinfunction "VCC_6") (pintype "bidirectional"))
      (node (ref "IC5") (pin "16") (pinfunction "VCC_16") (pintype "bidirectional"))
      (node (ref "IC6") (pin "1") (pinfunction "VCC_1") (pintype "power_in"))
      (node (ref "IC8") (pin "3") (pinfunction "VDD_3") (pintype "power_in"))
      (node (ref "IC9") (pin "3") (pinfunction "VDD_3") (pintype "power_in"))
      (node (ref "R10") (pin "1") (pinfunction "1_1") (pintype "passive"))
      (node (ref "R17") (pin "1") (pinfunction "1_1") (pintype "passive"))
      (node (ref "R18") (pin "1") (pinfunction "1_1") (pintype "passive"))
      (node (ref "R20") (pin "1") (pinfunction "1_1") (pintype "passive"))
      (node (ref "R7") (pin "1") (pinfunction "1_1") (pintype "passive"))
      (node (ref "U$10") (pin "OUT+") (pinfunction "OUT+_OUT+") (pintype "bidirectional"))
      (node (ref "U$5") (pin "+5V") (pinfunction "5V_+5V") (pintype "bidirectional"))
      (node (ref "U$6") (pin "BLA") (pinfunction "BLA_BLA") (pintype "bidirectional"))
      (node (ref "U$6") (pin "VDD") (pinfunction "VDD_VDD") (pintype "bidirectional"))
    )
    (net (code "79") (name "VLOAD_ATT") (class "Default")
      (node (ref "IC4") (pin "26") (pinfunction "PC3(ADC3)_26") (pintype "bidirectional"))
      (node (ref "R12") (pin "1") (pinfunction "1_1") (pintype "passive"))
      (node (ref "R13") (pin "2") (pinfunction "2_2") (pintype "passive"))
      (node (ref "VLOAD_ATT") (pin "TP") (pinfunction "TP_TP") (pintype "input"))
    )
    (net (code "80") (name "VLOAD_DROP") (class "Default")
      (node (ref "IC2") (pin "6") (pinfunction "-IN_6") (pintype "input"))
      (node (ref "IC4") (pin "25") (pinfunction "PC2(ADC2)_25") (pintype "bidirectional"))
      (node (ref "Q1") (pin "3") (pinfunction "S_3") (pintype "passive"))
      (node (ref "Q3") (pin "3") (pinfunction "S_3") (pintype "passive"))
      (node (ref "R4") (pin "1") (pinfunction "1_1") (pintype "passive"))
      (node (ref "R5") (pin "2") (pinfunction "2_2") (pintype "passive"))
      (node (ref "VLOAD_DROP") (pin "TP") (pinfunction "TP_TP") (pintype "input"))
    )
    (net (code "81") (name "unconnected-(H5-MOUNT-PadB3,0)") (class "Default")
      (node (ref "H5") (pin "B3,0") (pinfunction "MOUNT_B3,0") (pintype "passive"))
    )
    (net (code "82") (name "unconnected-(H6-MOUNT-PadB3,0)") (class "Default")
      (node (ref "H6") (pin "B3,0") (pinfunction "MOUNT_B3,0") (pintype "passive"))
    )
    (net (code "83") (name "unconnected-(IC3-GPA5-Pad26)") (class "Default")
      (node (ref "IC3") (pin "26") (pinfunction "GPA5_26") (pintype "bidirectional"))
    )
    (net (code "84") (name "unconnected-(IC3-GPA6-Pad27)") (class "Default")
      (node (ref "IC3") (pin "27") (pinfunction "GPA6_27") (pintype "bidirectional"))
    )
    (net (code "85") (name "unconnected-(IC3-GPA7-Pad28)") (class "Default")
      (node (ref "IC3") (pin "28") (pinfunction "GPA7_28") (pintype "bidirectional"))
    )
    (net (code "86") (name "unconnected-(IC3-INTA-Pad20)") (class "Default")
      (node (ref "IC3") (pin "20") (pinfunction "INTA_20") (pintype "output"))
    )
    (net (code "87") (name "unconnected-(IC3-INTB-Pad19)") (class "Default")
      (node (ref "IC3") (pin "19") (pinfunction "INTB_19") (pintype "output"))
    )
    (net (code "88") (name "unconnected-(IC4-ADC6-Pad19)") (class "Default")
      (node (ref "IC4") (pin "19") (pinfunction "ADC6_19") (pintype "bidirectional"))
    )
    (net (code "89") (name "unconnected-(IC4-ADC7-Pad22)") (class "Default")
      (node (ref "IC4") (pin "22") (pinfunction "ADC7_22") (pintype "bidirectional"))
    )
    (net (code "90") (name "unconnected-(IC5-T2IN-Pad10)") (class "Default")
      (node (ref "IC5") (pin "10") (pinfunction "T2IN_10") (pintype "input"))
    )
    (net (code "91") (name "unconnected-(IC5-T2OUT-Pad7)") (class "Default")
      (node (ref "IC5") (pin "7") (pinfunction "T2OUT_7") (pintype "output"))
    )
    (net (code "92") (name "unconnected-(JP2-Pad1)") (class "Default")
      (node (ref "JP2") (pin "1") (pinfunction "1_1") (pintype "passive"))
    )
    (net (code "93") (name "unconnected-(JP2-Pad7)") (class "Default")
      (node (ref "JP2") (pin "7") (pinfunction "7_7") (pintype "passive"))
    )
    (net (code "94") (name "unconnected-(JP2-Pad8)") (class "Default")
      (node (ref "JP2") (pin "8") (pinfunction "8_8") (pintype "passive"))
    )
    (net (code "95") (name "unconnected-(JP2-Pad9)") (class "Default")
      (node (ref "JP2") (pin "9") (pinfunction "9_9") (pintype "passive"))
    )
    (net (code "96") (name "unconnected-(KK1-K-PadK1)") (class "Default")
      (node (ref "KK1") (pin "K1") (pinfunction "K_K1") (pintype "passive"))
    )
    (net (code "97") (name "unconnected-(KK1-K-PadK2)") (class "Default")
      (node (ref "KK1") (pin "K2") (pinfunction "K_K2") (pintype "passive"))
    )
    (net (code "98") (name "unconnected-(KK3-K-PadK1)") (class "Default")
      (node (ref "KK3") (pin "K1") (pinfunction "K_K1") (pintype "passive"))
    )
    (net (code "99") (name "unconnected-(KK3-K-PadK2)") (class "Default")
      (node (ref "KK3") (pin "K2") (pinfunction "K_K2") (pintype "passive"))
    )
  )
)
